# LED_Strip.net
KiCad netlist of a schematic drawn in EAGLE
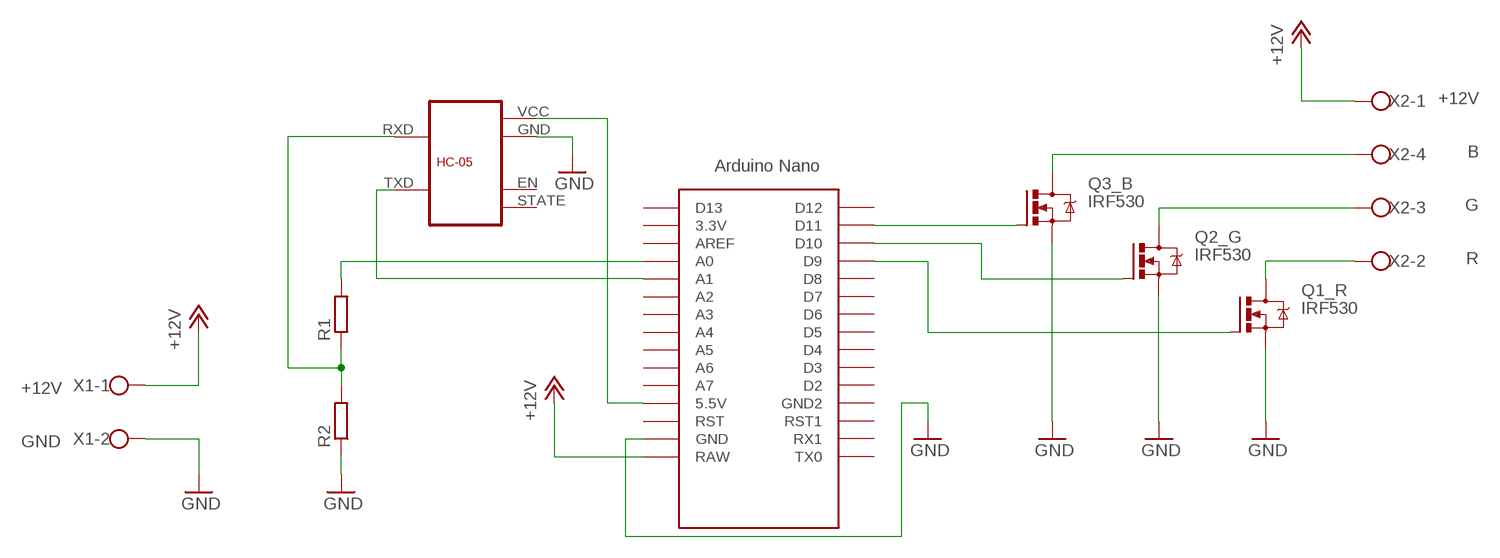
[diagram p0: schematic, sheet 1]

(export (version "E")
  (design (tool "Eeschema 10.0.6"))
  (components
    (comp (ref "Q1_R")
      (value "IRF530")
      (footprint "eagle-import:TO220BV")
      (libsource (lib "eagle-import") (part "IRF530"))
    )
    (comp (ref "Q2_G")
      (value "IRF530")
      (footprint "eagle-import:TO220BV")
      (libsource (lib "eagle-import") (part "IRF530"))
    )
    (comp (ref "Q3_B")
      (value "IRF530")
      (footprint "eagle-import:TO220BV")
      (libsource (lib "eagle-import") (part "IRF530"))
    )
    (comp (ref "R1")
      (value "R-EU0207/10")
      (footprint "eagle-import:0207_10")
      (libsource (lib "eagle-import") (part "R-EU0207/10"))
    )
    (comp (ref "R2")
      (value "R-EU0207/10")
      (footprint "eagle-import:0207_10")
      (libsource (lib "eagle-import") (part "R-EU0207/10"))
    )
    (comp (ref "U$1")
      (value "PAC_BLUETOOTH_HC-05")
      (footprint "eagle-import:BLUETOOTH_HC-05")
      (libsource (lib "eagle-import") (part "PAC_BLUETOOTH_HC-05"))
    )
    (comp (ref "U$2")
      (value "NANO")
      (footprint "eagle-import:NANO")
      (libsource (lib "eagle-import") (part "NANO"))
    )
    (comp (ref "X1")
      (value "W237-102_L")
      (footprint "eagle-import:W237-102_L")
      (libsource (lib "eagle-import") (part "W237-102_L"))
    )
    (comp (ref "X2")
      (value "W237-04P_R")
      (footprint "eagle-import:W237-4P_R")
      (libsource (lib "eagle-import") (part "W237-04P_R"))
    )
  )
  (nets
    (net (code "1") (name "+12V") (class "Default")
      (node (ref "U$2") (pin "RAW") (pinfunction "RAW_RAW") (pintype "bidirectional"))
      (node (ref "X1") (pin "1") (pinfunction "KL_1") (pintype "passive"))
      (node (ref "X2") (pin "1") (pinfunction "KL_1") (pintype "passive"))
    )
    (net (code "2") (name "GND") (class "Default")
      (node (ref "Q1_R") (pin "S") (pinfunction "S_S") (pintype "passive"))
      (node (ref "Q2_G") (pin "S") (pinfunction "S_S") (pintype "passive"))
      (node (ref "Q3_B") (pin "S") (pinfunction "S_S") (pintype "passive"))
      (node (ref "R2") (pin "1") (pinfunction "1_1") (pintype "passive"))
      (node (ref "U$1") (pin "GND") (pinfunction "GND_GND") (pintype "bidirectional"))
      (node (ref "U$2") (pin "GND") (pinfunction "GND_GND") (pintype "bidirectional"))
      (node (ref "X1") (pin "2") (pinfunction "KL_2") (pintype "passive"))
    )
    (net (code "3") (name "Net-(Q1_R-PadG)") (class "Default")
      (node (ref "Q1_R") (pin "G") (pinfunction "G_G") (pintype "passive"))
      (node (ref "U$2") (pin "D9") (pinfunction "D9_D9") (pintype "bidirectional"))
    )
    (net (code "4") (name "Net-(Q2_G-PadG)") (class "Default")
      (node (ref "Q2_G") (pin "G") (pinfunction "G_G") (pintype "passive"))
      (node (ref "U$2") (pin "D10") (pinfunction "D10_D10") (pintype "bidirectional"))
    )
    (net (code "5") (name "Net-(Q3_B-PadG)") (class "Default")
      (node (ref "Q3_B") (pin "G") (pinfunction "G_G") (pintype "passive"))
      (node (ref "U$2") (pin "D11") (pinfunction "D11_D11") (pintype "bidirectional"))
    )
    (net (code "6") (name "Net-(R1-Pad1)") (class "Default")
      (node (ref "R1") (pin "1") (pinfunction "1_1") (pintype "passive"))
      (node (ref "R2") (pin "2") (pinfunction "2_2") (pintype "passive"))
      (node (ref "U$1") (pin "RXD") (pinfunction "RXD_RXD") (pintype "bidirectional"))
    )
    (net (code "7") (name "Net-(R1-Pad2)") (class "Default")
      (node (ref "R1") (pin "2") (pinfunction "2_2") (pintype "passive"))
      (node (ref "U$2") (pin "A0") (pinfunction "A0_A0") (pintype "bidirectional"))
    )
    (net (code "8") (name "Net-(U$1-PadTXD)") (class "Default")
      (node (ref "U$1") (pin "TXD") (pinfunction "TXD_TXD") (pintype "bidirectional"))
      (node (ref "U$2") (pin "A1") (pinfunction "A1_A1") (pintype "bidirectional"))
    )
    (net (code "9") (name "Net-(U$2-5.5V)") (class "Default")
      (node (ref "U$1") (pin "VCC") (pinfunction "VCC_VCC") (pintype "bidirectional"))
      (node (ref "U$2") (pin "5V") (pinfunction "5.5V_5V") (pintype "bidirectional"))
    )
    (net (code "10") (name "Net-(X2B-KL)") (class "Default")
      (node (ref "Q1_R") (pin "D") (pinfunction "D_D") (pintype "passive"))
      (node (ref "X2") (pin "2") (pinfunction "KL_2") (pintype "passive"))
    )
    (net (code "11") (name "Net-(X2C-KL)") (class "Default")
      (node (ref "Q2_G") (pin "D") (pinfunction "D_D") (pintype "passive"))
      (node (ref "X2") (pin "3") (pinfunction "KL_3") (pintype "passive"))
    )
    (net (code "12") (name "Net-(X2D-KL)") (class "Default")
      (node (ref "Q3_B") (pin "D") (pinfunction "D_D") (pintype "passive"))
      (node (ref "X2") (pin "4") (pinfunction "KL_4") (pintype "passive"))
    )
    (net (code "13") (name "unconnected-(U$1-PadEN)") (class "Default")
      (node (ref "U$1") (pin "EN") (pinfunction "EN_EN") (pintype "bidirectional"))
    )
    (net (code "14") (name "unconnected-(U$1-PadSTATE)") (class "Default")
      (node (ref "U$1") (pin "STATE") (pinfunction "STATE_STATE") (pintype "bidirectional"))
    )
    (net (code "15") (name "unconnected-(U$2-GND2-PadGND1)") (class "Default")
      (node (ref "U$2") (pin "GND1") (pinfunction "GND2_GND1") (pintype "bidirectional"))
    )
    (net (code "16") (name "unconnected-(U$2-Pad3.3V)") (class "Default")
      (node (ref "U$2") (pin "3.3V") (pinfunction "3.3V_3.3V") (pintype "bidirectional"))
    )
    (net (code "17") (name "unconnected-(U$2-PadA2)") (class "Default")
      (node (ref "U$2") (pin "A2") (pinfunction "A2_A2") (pintype "bidirectional"))
    )
    (net (code "18") (name "unconnected-(U$2-PadA3)") (class "Default")
      (node (ref "U$2") (pin "A3") (pinfunction "A3_A3") (pintype "bidirectional"))
    )
    (net (code "19") (name "unconnected-(U$2-PadA4)") (class "Default")
      (node (ref "U$2") (pin "A4") (pinfunction "A4_A4") (pintype "bidirectional"))
    )
    (net (code "20") (name "unconnected-(U$2-PadA5)") (class "Default")
      (node (ref "U$2") (pin "A5") (pinfunction "A5_A5") (pintype "bidirectional"))
    )
    (net (code "21") (name "unconnected-(U$2-PadA6)") (class "Default")
      (node (ref "U$2") (pin "A6") (pinfunction "A6_A6") (pintype "bidirectional"))
    )
    (net (code "22") (name "unconnected-(U$2-PadA7)") (class "Default")
      (node (ref "U$2") (pin "A7") (pinfunction "A7_A7") (pintype "bidirectional"))
    )
    (net (code "23") (name "unconnected-(U$2-PadAREF)") (class "Default")
      (node (ref "U$2") (pin "AREF") (pinfunction "AREF_AREF") (pintype "bidirectional"))
    )
    (net (code "24") (name "unconnected-(U$2-PadD2)") (class "Default")
      (node (ref "U$2") (pin "D2") (pinfunction "D2_D2") (pintype "bidirectional"))
    )
    (net (code "25") (name "unconnected-(U$2-PadD3)") (class "Default")
      (node (ref "U$2") (pin "D3") (pinfunction "D3_D3") (pintype "bidirectional"))
    )
    (net (code "26") (name "unconnected-(U$2-PadD4)") (class "Default")
      (node (ref "U$2") (pin "D4") (pinfunction "D4_D4") (pintype "bidirectional"))
    )
    (net (code "27") (name "unconnected-(U$2-PadD5)") (class "Default")
      (node (ref "U$2") (pin "D5") (pinfunction "D5_D5") (pintype "bidirectional"))
    )
    (net (code "28") (name "unconnected-(U$2-PadD6)") (class "Default")
      (node (ref "U$2") (pin "D6") (pinfunction "D6_D6") (pintype "bidirectional"))
    )
    (net (code "29") (name "unconnected-(U$2-PadD7)") (class "Default")
      (node (ref "U$2") (pin "D7") (pinfunction "D7_D7") (pintype "bidirectional"))
    )
    (net (code "30") (name "unconnected-(U$2-PadD8)") (class "Default")
      (node (ref "U$2") (pin "D8") (pinfunction "D8_D8") (pintype "bidirectional"))
    )
    (net (code "31") (name "unconnected-(U$2-PadD12)") (class "Default")
      (node (ref "U$2") (pin "D12") (pinfunction "D12_D12") (pintype "bidirectional"))
    )
    (net (code "32") (name "unconnected-(U$2-PadD13)") (class "Default")
      (node (ref "U$2") (pin "D13") (pinfunction "D13_D13") (pintype "bidirectional"))
    )
    (net (code "33") (name "unconnected-(U$2-PadICSP1)") (class "Default")
      (node (ref "U$2") (pin "ICSP1") (pinfunction "ICSP1_ICSP1") (pintype "bidirectional"))
    )
    (net (code "34") (name "unconnected-(U$2-PadICSP2)") (class "Default")
      (node (ref "U$2") (pin "ICSP2") (pinfunction "ICSP2_ICSP2") (pintype "bidirectional"))
    )
    (net (code "35") (name "unconnected-(U$2-PadICSP3)") (class "Default")
      (node (ref "U$2") (pin "ICSP3") (pinfunction "ICSP3_ICSP3") (pintype "bidirectional"))
    )
    (net (code "36") (name "unconnected-(U$2-PadICSP4)") (class "Default")
      (node (ref "U$2") (pin "ICSP4") (pinfunction "ICSP4_ICSP4") (pintype "bidirectional"))
    )
    (net (code "37") (name "unconnected-(U$2-PadICSP5)") (class "Default")
      (node (ref "U$2") (pin "ICSP5") (pinfunction "ICSP5_ICSP5") (pintype "bidirectional"))
    )
    (net (code "38") (name "unconnected-(U$2-PadICSP6)") (class "Default")
      (node (ref "U$2") (pin "ICSP6") (pinfunction "ICSP6_ICSP6") (pintype "bidirectional"))
    )
    (net (code "39") (name "unconnected-(U$2-PadRST)") (class "Default")
      (node (ref "U$2") (pin "RST") (pinfunction "RST_RST") (pintype "bidirectional"))
    )
    (net (code "40") (name "unconnected-(U$2-PadRST1)") (class "Default")
      (node (ref "U$2") (pin "RST1") (pinfunction "RST1_RST1") (pintype "bidirectional"))
    )
    (net (code "41") (name "unconnected-(U$2-PadRX1)") (class "Default")
      (node (ref "U$2") (pin "RX1") (pinfunction "RX1_RX1") (pintype "bidirectional"))
    )
    (net (code "42") (name "unconnected-(U$2-PadTX0)") (class "Default")
      (node (ref "U$2") (pin "TX0") (pinfunction "TX0_TX0") (pintype "bidirectional"))
    )
  )
)
